# power-dist-board2.net
KiCad netlist of a schematic drawn in EAGLE
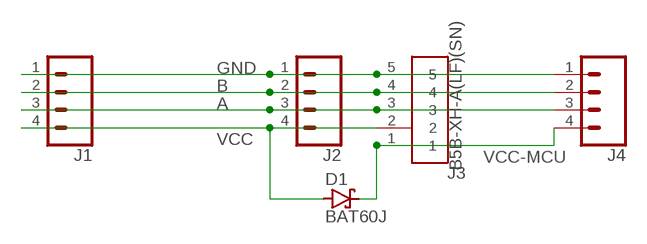
[diagram p0: schematic, sheet 1]

(export (version "E")
  (design (tool "Eeschema 10.0.6"))
  (components
    (comp (ref "D1")
      (value "BAT60J")
      (footprint "eagle-import:SOD323_ST")
      (libsource (lib "eagle-import") (part "BAT60J"))
    )
    (comp (ref "J1")
      (value "CONN_04")
      (footprint "eagle-import:1X04")
      (libsource (lib "eagle-import") (part "CONN_04"))
    )
    (comp (ref "J2")
      (value "CONN_04")
      (footprint "eagle-import:1X04")
      (libsource (lib "eagle-import") (part "CONN_04"))
    )
    (comp (ref "J3")
      (value "B5B-XH-A(LF)(SN)")
      (footprint "eagle-import:JST_B5B-XH-A(LF)(SN)")
      (libsource (lib "eagle-import") (part "B5B-XH-A(LF)(SN)"))
    )
    (comp (ref "J4")
      (value "CONN_04")
      (footprint "eagle-import:1X04")
      (libsource (lib "eagle-import") (part "CONN_04"))
    )
  )
  (nets
    (net (code "1") (name "/A") (class "Default")
      (node (ref "J1") (pin "3") (pinfunction "3_3") (pintype "passive"))
      (node (ref "J2") (pin "3") (pinfunction "3_3") (pintype "passive"))
      (node (ref "J3") (pin "3") (pinfunction "3_3") (pintype "passive"))
      (node (ref "J4") (pin "3") (pinfunction "3_3") (pintype "passive"))
    )
    (net (code "2") (name "/B") (class "Default")
      (node (ref "J1") (pin "2") (pinfunction "2_2") (pintype "passive"))
      (node (ref "J2") (pin "2") (pinfunction "2_2") (pintype "passive"))
      (node (ref "J3") (pin "4") (pinfunction "4_4") (pintype "passive"))
      (node (ref "J4") (pin "2") (pinfunction "2_2") (pintype "passive"))
    )
    (net (code "3") (name "/GND") (class "Default")
      (node (ref "J1") (pin "1") (pinfunction "1_1") (pintype "passive"))
      (node (ref "J2") (pin "1") (pinfunction "1_1") (pintype "passive"))
      (node (ref "J3") (pin "5") (pinfunction "5_5") (pintype "passive"))
      (node (ref "J4") (pin "1") (pinfunction "1_1") (pintype "passive"))
    )
    (net (code "4") (name "/VCC") (class "Default")
      (node (ref "D1") (pin "A") (pinfunction "A_A") (pintype "passive"))
      (node (ref "J1") (pin "4") (pinfunction "4_4") (pintype "passive"))
      (node (ref "J2") (pin "4") (pinfunction "4_4") (pintype "passive"))
      (node (ref "J3") (pin "2") (pinfunction "2_2") (pintype "passive"))
    )
    (net (code "5") (name "/VCC-MCU") (class "Default")
      (node (ref "D1") (pin "C") (pinfunction "C_C") (pintype "passive"))
      (node (ref "J3") (pin "1") (pinfunction "1_1") (pintype "passive"))
      (node (ref "J4") (pin "4") (pinfunction "4_4") (pintype "passive"))
    )
  )
)
